# 4_-MCU_MEMORY.net
KiCad netlist of a schematic drawn in Altium Designer
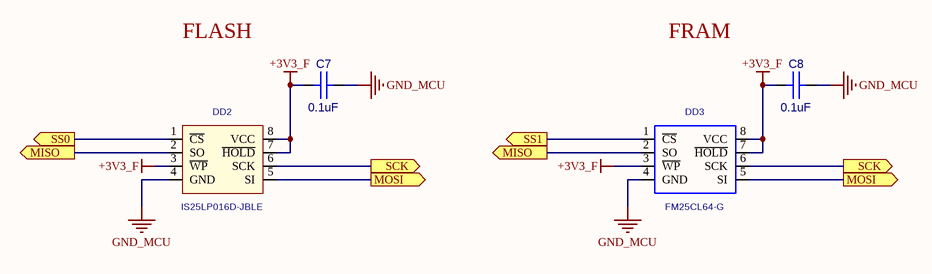
[diagram p0: [4]-MCU_MEMORY.SchDoc]

(export (version "E")
  (design (tool "Eeschema 10.0.6"))
  (components
    (comp (ref "C7")
      (value "0.1uF")
      (footprint "CC0603")
      (description "CC0603")
      (libsource (lib "fizik_lib") (part "CC0603"))
    )
    (comp (ref "C8")
      (value "0.1uF")
      (footprint "CC0603")
      (description "CC0603")
      (libsource (lib "fizik_lib") (part "CC0603"))
    )
    (comp (ref "DD2")
      (value "IS25LP016D-JBLE")
      (footprint "EIAJ_SO8")
      (description "S25FL016A0LMFI01")
      (libsource (lib "fizik_lib") (part "S25FL016A0LMFI01"))
    )
    (comp (ref "DD3")
      (value "FM25CL64-G")
      (footprint "SO-8")
      (libsource (lib "fizik_lib") (part "FM25CL64-G"))
    )
  )
  (nets
    (net (code "1") (name "+3V3_F") (class "Default")
      (node (ref "C7") (pin "1") (pinfunction "A_1") (pintype "passive"))
      (node (ref "C8") (pin "1") (pinfunction "A_1") (pintype "passive"))
      (node (ref "DD2") (pin "3") (pinfunction "~{WP}_3") (pintype "passive"))
      (node (ref "DD2") (pin "7") (pinfunction "~{HOLD}_7") (pintype "passive"))
      (node (ref "DD2") (pin "8") (pinfunction "VCC_8") (pintype "passive"))
      (node (ref "DD3") (pin "3") (pinfunction "~{WP}_3") (pintype "passive"))
      (node (ref "DD3") (pin "7") (pinfunction "~{HOLD}_7") (pintype "passive"))
      (node (ref "DD3") (pin "8") (pinfunction "VCC_8") (pintype "passive"))
    )
    (net (code "2") (name "/MISO") (class "Default")
      (node (ref "DD2") (pin "2") (pinfunction "SO_2") (pintype "passive"))
      (node (ref "DD3") (pin "2") (pinfunction "SO_2") (pintype "passive"))
    )
    (net (code "3") (name "/MOSI") (class "Default")
      (node (ref "DD2") (pin "5") (pinfunction "SI_5") (pintype "passive"))
      (node (ref "DD3") (pin "5") (pinfunction "SI_5") (pintype "passive"))
    )
    (net (code "4") (name "/SCK") (class "Default")
      (node (ref "DD2") (pin "6") (pinfunction "SCK_6") (pintype "passive"))
      (node (ref "DD3") (pin "6") (pinfunction "SCK_6") (pintype "passive"))
    )
    (net (code "5") (name "/SS0") (class "Default")
      (node (ref "DD2") (pin "1") (pinfunction "~{CS}_1") (pintype "passive"))
    )
    (net (code "6") (name "/SS1") (class "Default")
      (node (ref "DD3") (pin "1") (pinfunction "~{CS}_1") (pintype "passive"))
    )
    (net (code "7") (name "GND_MCU") (class "Default")
      (node (ref "C7") (pin "2") (pinfunction "B_2") (pintype "passive"))
      (node (ref "C8") (pin "2") (pinfunction "B_2") (pintype "passive"))
      (node (ref "DD2") (pin "4") (pinfunction "GND_4") (pintype "passive"))
      (node (ref "DD3") (pin "4") (pinfunction "GND_4") (pintype "passive"))
    )
  )
)
